# Schematic.net
KiCad netlist of a schematic drawn in Altium Designer
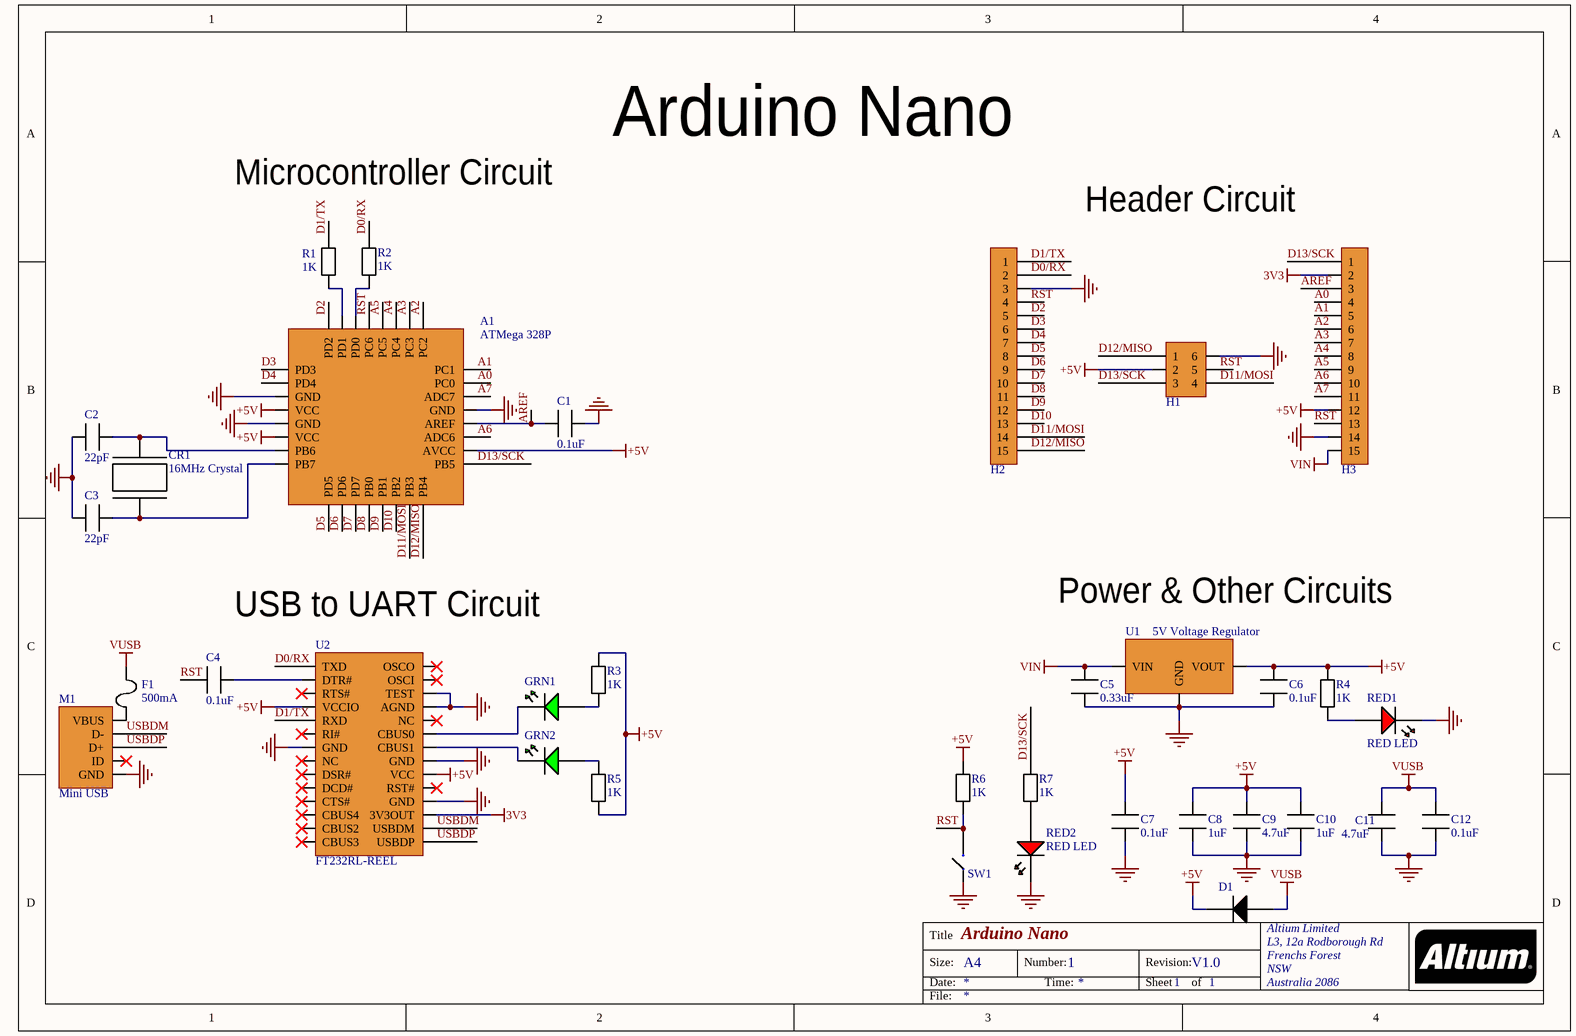
[diagram p0: Schematic.SchDoc]

(export (version "E")
  (design (tool "Eeschema 10.0.6"))
  (components
    (comp (ref "A1")
      (value "ATMega 328P")
      (footprint "ATmega 328P")
      (fields
        (field (name "MANUFACTURER") "Microchip / Atmel")
        (field (name "MANUFACTURER PART NUMBER") "ATMEGA328P-AUR")
      )
      (libsource (lib "Schematic Library") (part "ATMEGA328P-AUR"))
    )
    (comp (ref "C1")
      (value "0.1uF")
      (footprint "0.1uF Capacitor")
      (description "TAIYO YUDEN - EMK105BJ104KV-F - CERAMIC CAPACITOR, 0.1UF, 16V, X5R, 10%, 0402, FULL REEL")
      (fields
        (field (name "MANUFACTURER") "Taiyo Yuden")
        (field (name "MANUFACTURER PART NUMBER") "EMK105BJ104KV-F")
      )
      (libsource (lib "Schematic Library") (part "EMK105BJ104KV-F"))
    )
    (comp (ref "C2")
      (value "22pF")
      (footprint "22pF")
      (description "Cap Ceramic 22pF 50V C0G 1% SMD 0402 125C Paper T/R")
      (fields
        (field (name "MANUFACTURER") "Kyocera AVX")
        (field (name "MANUFACTURER PART NUMBER") "04025A220FAT2A")
      )
      (libsource (lib "Schematic Library") (part "04025A220FAT2A"))
    )
    (comp (ref "C3")
      (value "22pF")
      (footprint "22pF")
      (description "Cap Ceramic 22pF 50V C0G 1% SMD 0402 125C Paper T/R")
      (fields
        (field (name "MANUFACTURER") "Kyocera AVX")
        (field (name "MANUFACTURER PART NUMBER") "04025A220FAT2A")
      )
      (libsource (lib "Schematic Library") (part "04025A220FAT2A"))
    )
    (comp (ref "C4")
      (value "0.1uF")
      (footprint "0.1uF Capacitor")
      (description "TAIYO YUDEN - EMK105BJ104KV-F - CERAMIC CAPACITOR, 0.1UF, 16V, X5R, 10%, 0402, FULL REEL")
      (fields
        (field (name "MANUFACTURER") "Taiyo Yuden")
        (field (name "MANUFACTURER PART NUMBER") "EMK105BJ104KV-F")
      )
      (libsource (lib "Schematic Library") (part "EMK105BJ104KV-F"))
    )
    (comp (ref "C5")
      (value "0.33uF")
      (footprint "0.33uF Capacitor")
      (description "Automotive Grade")
      (fields
        (field (name "MANUFACTURER") "TDK")
        (field (name "MANUFACTURER PART NUMBER") "CGA2B1X7S1C334K050BC")
      )
      (libsource (lib "Schematic Library") (part "CGA2B1X7S1C334K050BC"))
    )
    (comp (ref "C6")
      (value "0.1uF")
      (footprint "0.1uF Capacitor")
      (description "TAIYO YUDEN - EMK105BJ104KV-F - CERAMIC CAPACITOR, 0.1UF, 16V, X5R, 10%, 0402, FULL REEL")
      (fields
        (field (name "MANUFACTURER") "Taiyo Yuden")
        (field (name "MANUFACTURER PART NUMBER") "EMK105BJ104KV-F")
      )
      (libsource (lib "Schematic Library") (part "EMK105BJ104KV-F"))
    )
    (comp (ref "C7")
      (value "0.1uF")
      (footprint "0.1uF Capacitor")
      (description "TAIYO YUDEN - EMK105BJ104KV-F - CERAMIC CAPACITOR, 0.1UF, 16V, X5R, 10%, 0402, FULL REEL")
      (fields
        (field (name "MANUFACTURER") "Taiyo Yuden")
        (field (name "MANUFACTURER PART NUMBER") "EMK105BJ104KV-F")
      )
      (libsource (lib "Schematic Library") (part "EMK105BJ104KV-F"))
    )
    (comp (ref "C8")
      (value "1uF")
      (footprint "1uF Capacitor")
      (description "LMK105BJ105KV-F")
      (fields (field (name "MANUFACTURER") "Taiyo Yuden") (field (name "TOLERANCE") "10%"))
      (libsource (lib "Schematic Library") (part "LMK105BJ105KV-F"))
    )
    (comp (ref "C9")
      (value "4.7uF")
      (footprint "4.7uF Capacitor")
      (description "CAP CER 4.7UF 6.3V X5R 0402")
      (fields
        (field (name "MANUFACTURER") "Taiyo Yuden")
        (field (name "MANUFACTURER PART NUMBER") "JMK105BBJ475MVHF")
      )
      (libsource (lib "Schematic Library") (part "JMK105BBJ475MVHF"))
    )
    (comp (ref "C10")
      (value "1uF")
      (footprint "1uF Capacitor")
      (description "LMK105BJ105KV-F")
      (fields (field (name "MANUFACTURER") "Taiyo Yuden") (field (name "TOLERANCE") "10%"))
      (libsource (lib "Schematic Library") (part "LMK105BJ105KV-F"))
    )
    (comp (ref "C11")
      (value "4.7uF")
      (footprint "4.7uF Capacitor")
      (description "CAP CER 4.7UF 6.3V X5R 0402")
      (fields
        (field (name "MANUFACTURER") "Taiyo Yuden")
        (field (name "MANUFACTURER PART NUMBER") "JMK105BBJ475MVHF")
      )
      (libsource (lib "Schematic Library") (part "JMK105BBJ475MVHF"))
    )
    (comp (ref "C12")
      (value "0.1uF")
      (footprint "0.1uF Capacitor")
      (description "TAIYO YUDEN - EMK105BJ104KV-F - CERAMIC CAPACITOR, 0.1UF, 16V, X5R, 10%, 0402, FULL REEL")
      (fields
        (field (name "MANUFACTURER") "Taiyo Yuden")
        (field (name "MANUFACTURER PART NUMBER") "EMK105BJ104KV-F")
      )
      (libsource (lib "Schematic Library") (part "EMK105BJ104KV-F"))
    )
    (comp (ref "CR1")
      (value "16MHz Crystal")
      (footprint "16MHz Crystal")
      (description "CRYSTAL 16.0000MHZ 20PF SMD")
      (fields
        (field (name "MANUFACTURER") "ECS International")
        (field (name "MANUFACTURER PART NUMBER") "ECS-160-20-5PX-TR")
      )
      (libsource (lib "Schematic Library") (part "ECS-160-20-5PX-TR"))
    )
    (comp (ref "D1")
      (value "Diode")
      (footprint "Diode")
      (description "MULTICOMP PRO - BAT54LP-7 - DIODE, ULTRAFAST RECOVERY, 100mA, 30V, DFN1006")
      (fields (field (name "MANUFACTURER") "Diodes") (field (name "MANUFACTURER PART NUMBER") "BAT54LP-7"))
      (libsource (lib "Schematic Library") (part "BAT54LP-7"))
    )
    (comp (ref "F1")
      (value "500mA")
      (footprint "Fuse")
      (description "Fuse Chip 0.5A 125V Very Fast 2-Pin Solder Pad Surface Mount T/R")
      (fields (field (name "MANUFACTURER") "Bel") (field (name "MANUFACTURER PART NUMBER") "C1Q500"))
      (libsource (lib "Schematic Library") (part "C1Q500"))
    )
    (comp (ref "GRN1")
      (value "GREEN LED")
      (footprint "GREEN LED")
      (description "LED GREEN CLEAR 0402 SMD")
      (fields
        (field (name "MANUFACTURER") "Wurth Electronics")
        (field (name "MANUFACTURER PART NUMBER") "150040VS73240")
      )
      (libsource (lib "Schematic Library") (part "150040VS73240"))
    )
    (comp (ref "GRN2")
      (value "GREEN LED")
      (footprint "GREEN LED")
      (description "LED GREEN CLEAR 0402 SMD")
      (fields
        (field (name "MANUFACTURER") "Wurth Electronics")
        (field (name "MANUFACTURER PART NUMBER") "150040VS73240")
      )
      (libsource (lib "Schematic Library") (part "150040VS73240"))
    )
    (comp (ref "H1")
      (value "3x3")
      (footprint "3x3 Header")
      (description "CONN HEADER VERT 6POS 2.54MM")
      (fields
        (field (name "MANUFACTURER") "Wurth Electronics")
        (field (name "MANUFACTURER PART NUMBER") "61300621121")
      )
      (libsource (lib "Schematic Library") (part "61300621121"))
    )
    (comp (ref "H2")
      (value "15x1")
      (footprint "15x1 Header")
      (fields
        (field (name "MANUFACTURER") "Wurth Electronics")
        (field (name "MANUFACTURER PART NUMBER") "61301511121")
      )
      (libsource (lib "") (part "61301511121_1"))
    )
    (comp (ref "H3")
      (value "15x1")
      (footprint "15x1 Header")
      (fields
        (field (name "MANUFACTURER") "Wurth Electronics")
        (field (name "MANUFACTURER PART NUMBER") "61301511121")
      )
      (libsource (lib "Schematic Library") (part "61301511121"))
    )
    (comp (ref "M1")
      (value "Mini USB")
      (footprint "Mini USB")
      (description "CONN RCPT USB2.0 MINI B SMD R/A")
      (fields
        (field (name "MANUFACTURER") "Wurth Electronics")
        (field (name "MANUFACTURER PART NUMBER") "65100516121")
      )
      (libsource (lib "Schematic Library") (part "65100516121"))
    )
    (comp (ref "R1")
      (value "1K")
      (footprint "1K Resistor")
      (description "RES 1K OHM 1% 1/16W 0402")
      (fields
        (field (name "MANUFACTURER") "Stackpole Electronics")
        (field (name "MANUFACTURER PART NUMBER") "RMCF0402FT1K00")
      )
      (libsource (lib "Schematic Library") (part "RMCF0402FT1K00"))
    )
    (comp (ref "R2")
      (value "1K")
      (footprint "1K Resistor")
      (description "RES 1K OHM 1% 1/16W 0402")
      (fields
        (field (name "MANUFACTURER") "Stackpole Electronics")
        (field (name "MANUFACTURER PART NUMBER") "RMCF0402FT1K00")
      )
      (libsource (lib "Schematic Library") (part "RMCF0402FT1K00"))
    )
    (comp (ref "R3")
      (value "1K")
      (footprint "1K Resistor")
      (description "RES 1K OHM 1% 1/16W 0402")
      (fields
        (field (name "MANUFACTURER") "Stackpole Electronics")
        (field (name "MANUFACTURER PART NUMBER") "RMCF0402FT1K00")
      )
      (libsource (lib "Schematic Library") (part "RMCF0402FT1K00"))
    )
    (comp (ref "R4")
      (value "1K")
      (footprint "1K Resistor")
      (description "RES 1K OHM 1% 1/16W 0402")
      (fields
        (field (name "MANUFACTURER") "Stackpole Electronics")
        (field (name "MANUFACTURER PART NUMBER") "RMCF0402FT1K00")
      )
      (libsource (lib "Schematic Library") (part "RMCF0402FT1K00"))
    )
    (comp (ref "R5")
      (value "1K")
      (footprint "1K Resistor")
      (description "RES 1K OHM 1% 1/16W 0402")
      (fields
        (field (name "MANUFACTURER") "Stackpole Electronics")
        (field (name "MANUFACTURER PART NUMBER") "RMCF0402FT1K00")
      )
      (libsource (lib "Schematic Library") (part "RMCF0402FT1K00"))
    )
    (comp (ref "R6")
      (value "1K")
      (footprint "1K Resistor")
      (description "RES 1K OHM 1% 1/16W 0402")
      (fields
        (field (name "MANUFACTURER") "Stackpole Electronics")
        (field (name "MANUFACTURER PART NUMBER") "RMCF0402FT1K00")
      )
      (libsource (lib "Schematic Library") (part "RMCF0402FT1K00"))
    )
    (comp (ref "R7")
      (value "1K")
      (footprint "1K Resistor")
      (description "RES 1K OHM 1% 1/16W 0402")
      (fields
        (field (name "MANUFACTURER") "Stackpole Electronics")
        (field (name "MANUFACTURER PART NUMBER") "RMCF0402FT1K00")
      )
      (libsource (lib "Schematic Library") (part "RMCF0402FT1K00"))
    )
    (comp (ref "RED1")
      (value "RED LED")
      (footprint "RED LED")
      (description "LED RED CLEAR 0402 SMD")
      (fields
        (field (name "MANUFACTURER") "Wurth Electronics")
        (field (name "MANUFACTURER PART NUMBER") "150040RS73240")
      )
      (libsource (lib "Schematic Library") (part "150040RS73240"))
    )
    (comp (ref "RED2")
      (value "RED LED")
      (footprint "RED LED")
      (description "LED RED CLEAR 0402 SMD")
      (fields
        (field (name "MANUFACTURER") "Wurth Electronics")
        (field (name "MANUFACTURER PART NUMBER") "150040RS73240")
      )
      (libsource (lib "Schematic Library") (part "150040RS73240"))
    )
    (comp (ref "SW1")
      (value "Push Button")
      (footprint "Push Button")
      (description "SWITCH TACTILE SPST-NO 0.05A 12V")
      (fields
        (field (name "MANUFACTURER") "Wurth Electronics")
        (field (name "MANUFACTURER PART NUMBER") "434121043836")
      )
      (libsource (lib "Schematic Library") (part "434121043836"))
    )
    (comp (ref "U1")
      (value "5V Voltage Regulator")
      (footprint "Voltage Regulator")
      (description "TEXAS INSTRUMENTS - UA78L05ACPK - LINEAR VOLT REG, 5V, 0.1A, SOT-89-3")
      (fields
        (field (name "MANUFACTURER") "Texas Instruments")
        (field (name "MANUFACTURER PART NUMBER") "UA78L05ACPK")
      )
      (libsource (lib "Schematic Library") (part "UA78L05ACPK"))
    )
    (comp (ref "U2")
      (value "FT232RL-REEL")
      (footprint "FTDI")
      (description "FTDI - FT232RL-REEL - Interface Bridges, USB to UART, 1.8 V, 5.25 V, SSOP, 28 Pins, -40 °C")
      (fields (field (name "MANUFACTURER") "FTDI") (field (name "VOLTAGE") "5V"))
      (libsource (lib "Schematic Library") (part "FT232RL-REEL"))
    )
  )
  (nets
    (net (code "1") (name "+5V") (class "Default")
      (node (ref "A1") (pin "18") (pinfunction "AVCC_18") (pintype "passive"))
      (node (ref "A1") (pin "4") (pinfunction "VCC_4") (pintype "passive"))
      (node (ref "A1") (pin "6") (pinfunction "VCC_6") (pintype "passive"))
      (node (ref "C10") (pin "2") (pinfunction "2_2") (pintype "passive"))
      (node (ref "C6") (pin "2") (pinfunction "2_2") (pintype "passive"))
      (node (ref "C7") (pin "1") (pinfunction "1_1") (pintype "passive"))
      (node (ref "C8") (pin "2") (pinfunction "2_2") (pintype "passive"))
      (node (ref "C9") (pin "2") (pinfunction "2_2") (pintype "passive"))
      (node (ref "D1") (pin "1") (pinfunction "1_1") (pintype "passive"))
      (node (ref "H1") (pin "2") (pinfunction "2_2") (pintype "passive"))
      (node (ref "H3") (pin "12") (pinfunction "12_12") (pintype "passive"))
      (node (ref "R3") (pin "2") (pinfunction "2_2") (pintype "passive"))
      (node (ref "R4") (pin "2") (pinfunction "2_2") (pintype "passive"))
      (node (ref "R5") (pin "1") (pinfunction "1_1") (pintype "passive"))
      (node (ref "R6") (pin "2") (pinfunction "2_2") (pintype "passive"))
      (node (ref "U1") (pin "3") (pinfunction "VOUT_3") (pintype "passive"))
      (node (ref "U2") (pin "20") (pinfunction "VCC_20") (pintype "passive"))
      (node (ref "U2") (pin "4") (pinfunction "VCCIO_4") (pintype "passive"))
    )
    (net (code "2") (name "/A0") (class "Default")
      (node (ref "A1") (pin "23") (pinfunction "PC0_23") (pintype "passive"))
      (node (ref "H3") (pin "4") (pinfunction "4_4") (pintype "passive"))
    )
    (net (code "3") (name "/A1") (class "Default")
      (node (ref "A1") (pin "24") (pinfunction "PC1_24") (pintype "passive"))
      (node (ref "H3") (pin "5") (pinfunction "5_5") (pintype "passive"))
    )
    (net (code "4") (name "/A2") (class "Default")
      (node (ref "A1") (pin "25") (pinfunction "PC2_25") (pintype "passive"))
      (node (ref "H3") (pin "6") (pinfunction "6_6") (pintype "passive"))
    )
    (net (code "5") (name "/A3") (class "Default")
      (node (ref "A1") (pin "26") (pinfunction "PC3_26") (pintype "passive"))
      (node (ref "H3") (pin "7") (pinfunction "7_7") (pintype "passive"))
    )
    (net (code "6") (name "/A4") (class "Default")
      (node (ref "A1") (pin "27") (pinfunction "PC4_27") (pintype "passive"))
      (node (ref "H3") (pin "8") (pinfunction "8_8") (pintype "passive"))
    )
    (net (code "7") (name "/A5") (class "Default")
      (node (ref "A1") (pin "28") (pinfunction "PC5_28") (pintype "passive"))
      (node (ref "H3") (pin "9") (pinfunction "9_9") (pintype "passive"))
    )
    (net (code "8") (name "/A6") (class "Default")
      (node (ref "A1") (pin "19") (pinfunction "ADC6_19") (pintype "passive"))
      (node (ref "H3") (pin "10") (pinfunction "10_10") (pintype "passive"))
    )
    (net (code "9") (name "/A7") (class "Default")
      (node (ref "A1") (pin "22") (pinfunction "ADC7_22") (pintype "passive"))
      (node (ref "H3") (pin "11") (pinfunction "11_11") (pintype "passive"))
    )
    (net (code "10") (name "/AREF") (class "Default")
      (node (ref "A1") (pin "20") (pinfunction "AREF_20") (pintype "passive"))
      (node (ref "C1") (pin "1") (pinfunction "1_1") (pintype "passive"))
      (node (ref "H3") (pin "3") (pinfunction "3_3") (pintype "passive"))
    )
    (net (code "11") (name "/D0{slash}RX") (class "Default")
      (node (ref "H2") (pin "2") (pinfunction "2_2") (pintype "passive"))
      (node (ref "R2") (pin "1") (pinfunction "1_1") (pintype "passive"))
      (node (ref "U2") (pin "1") (pinfunction "TXD_1") (pintype "passive"))
    )
    (net (code "12") (name "/D1{slash}TX") (class "Default")
      (node (ref "H2") (pin "1") (pinfunction "1_1") (pintype "passive"))
      (node (ref "R1") (pin "2") (pinfunction "2_2") (pintype "passive"))
      (node (ref "U2") (pin "5") (pinfunction "RXD_5") (pintype "passive"))
    )
    (net (code "13") (name "/D2") (class "Default")
      (node (ref "A1") (pin "32") (pinfunction "PD2_32") (pintype "passive"))
      (node (ref "H2") (pin "5") (pinfunction "5_5") (pintype "passive"))
    )
    (net (code "14") (name "/D3") (class "Default")
      (node (ref "A1") (pin "1") (pinfunction "PD3_1") (pintype "passive"))
      (node (ref "H2") (pin "6") (pinfunction "6_6") (pintype "passive"))
    )
    (net (code "15") (name "/D4") (class "Default")
      (node (ref "A1") (pin "2") (pinfunction "PD4_2") (pintype "passive"))
      (node (ref "H2") (pin "7") (pinfunction "7_7") (pintype "passive"))
    )
    (net (code "16") (name "/D5") (class "Default")
      (node (ref "A1") (pin "9") (pinfunction "PD5_9") (pintype "passive"))
      (node (ref "H2") (pin "8") (pinfunction "8_8") (pintype "passive"))
    )
    (net (code "17") (name "/D6") (class "Default")
      (node (ref "A1") (pin "10") (pinfunction "PD6_10") (pintype "passive"))
      (node (ref "H2") (pin "9") (pinfunction "9_9") (pintype "passive"))
    )
    (net (code "18") (name "/D7") (class "Default")
      (node (ref "A1") (pin "11") (pinfunction "PD7_11") (pintype "passive"))
      (node (ref "H2") (pin "10") (pinfunction "10_10") (pintype "passive"))
    )
    (net (code "19") (name "/D8") (class "Default")
      (node (ref "A1") (pin "12") (pinfunction "PB0_12") (pintype "passive"))
      (node (ref "H2") (pin "11") (pinfunction "11_11") (pintype "passive"))
    )
    (net (code "20") (name "/D9") (class "Default")
      (node (ref "A1") (pin "13") (pinfunction "PB1_13") (pintype "passive"))
      (node (ref "H2") (pin "12") (pinfunction "12_12") (pintype "passive"))
    )
    (net (code "21") (name "/D10") (class "Default")
      (node (ref "A1") (pin "14") (pinfunction "PB2_14") (pintype "passive"))
      (node (ref "H2") (pin "13") (pinfunction "13_13") (pintype "passive"))
    )
    (net (code "22") (name "/D11{slash}MOSI") (class "Default")
      (node (ref "A1") (pin "15") (pinfunction "PB3_15") (pintype "passive"))
      (node (ref "H1") (pin "4") (pinfunction "4_4") (pintype "passive"))
      (node (ref "H2") (pin "14") (pinfunction "14_14") (pintype "passive"))
    )
    (net (code "23") (name "/D12{slash}MISO") (class "Default")
      (node (ref "A1") (pin "16") (pinfunction "PB4_16") (pintype "passive"))
      (node (ref "H1") (pin "1") (pinfunction "1_1") (pintype "passive"))
      (node (ref "H2") (pin "15") (pinfunction "15_15") (pintype "passive"))
    )
    (net (code "24") (name "/D13{slash}SCK") (class "Default")
      (node (ref "A1") (pin "17") (pinfunction "PB5_17") (pintype "passive"))
      (node (ref "H1") (pin "3") (pinfunction "3_3") (pintype "passive"))
      (node (ref "H3") (pin "1") (pinfunction "1_1") (pintype "passive"))
      (node (ref "R7") (pin "2") (pinfunction "2_2") (pintype "passive"))
    )
    (net (code "25") (name "/RST") (class "Default")
      (node (ref "A1") (pin "29") (pinfunction "PC6_29") (pintype "passive"))
      (node (ref "C4") (pin "1") (pinfunction "1_1") (pintype "passive"))
      (node (ref "H1") (pin "5") (pinfunction "5_5") (pintype "passive"))
      (node (ref "H2") (pin "4") (pinfunction "4_4") (pintype "passive"))
      (node (ref "H3") (pin "13") (pinfunction "13_13") (pintype "passive"))
      (node (ref "R6") (pin "1") (pinfunction "1_1") (pintype "passive"))
      (node (ref "SW1") (pin "2") (pinfunction "2_2") (pintype "passive"))
    )
    (net (code "26") (name "/USBDM") (class "Default")
      (node (ref "M1") (pin "2") (pinfunction "D-_2") (pintype "passive"))
      (node (ref "U2") (pin "16") (pinfunction "USBDM_16") (pintype "passive"))
    )
    (net (code "27") (name "/USBDP") (class "Default")
      (node (ref "M1") (pin "3") (pinfunction "D+_3") (pintype "passive"))
      (node (ref "U2") (pin "15") (pinfunction "USBDP_15") (pintype "passive"))
    )
    (net (code "28") (name "3V3") (class "Default")
      (node (ref "H3") (pin "2") (pinfunction "2_2") (pintype "passive"))
      (node (ref "U2") (pin "17") (pinfunction "3V3OUT_17") (pintype "passive"))
    )
    (net (code "29") (name "GND") (class "Default")
      (node (ref "A1") (pin "21") (pinfunction "GND_21") (pintype "passive"))
      (node (ref "A1") (pin "3") (pinfunction "GND_3") (pintype "passive"))
      (node (ref "A1") (pin "5") (pinfunction "GND_5") (pintype "passive"))
      (node (ref "C1") (pin "2") (pinfunction "2_2") (pintype "passive"))
      (node (ref "C10") (pin "1") (pinfunction "1_1") (pintype "passive"))
      (node (ref "C11") (pin "1") (pinfunction "1_1") (pintype "passive"))
      (node (ref "C12") (pin "1") (pinfunction "1_1") (pintype "passive"))
      (node (ref "C2") (pin "1") (pinfunction "1_1") (pintype "passive"))
      (node (ref "C3") (pin "2") (pinfunction "2_2") (pintype "passive"))
      (node (ref "C5") (pin "1") (pinfunction "1_1") (pintype "passive"))
      (node (ref "C6") (pin "1") (pinfunction "1_1") (pintype "passive"))
      (node (ref "C7") (pin "2") (pinfunction "2_2") (pintype "passive"))
      (node (ref "C8") (pin "1") (pinfunction "1_1") (pintype "passive"))
      (node (ref "C9") (pin "1") (pinfunction "1_1") (pintype "passive"))
      (node (ref "H1") (pin "6") (pinfunction "6_6") (pintype "passive"))
      (node (ref "H2") (pin "3") (pinfunction "3_3") (pintype "passive"))
      (node (ref "H3") (pin "14") (pinfunction "14_14") (pintype "passive"))
      (node (ref "M1") (pin "5") (pinfunction "GND_5") (pintype "passive"))
      (node (ref "RED1") (pin "1") (pinfunction "1_1") (pintype "passive"))
      (node (ref "RED2") (pin "1") (pinfunction "1_1") (pintype "passive"))
      (node (ref "SW1") (pin "1") (pinfunction "1_1") (pintype "passive"))
      (node (ref "U1") (pin "2") (pinfunction "GND_2") (pintype "passive"))
      (node (ref "U2") (pin "18") (pinfunction "GND_18") (pintype "passive"))
      (node (ref "U2") (pin "21") (pinfunction "GND_21") (pintype "passive"))
      (node (ref "U2") (pin "25") (pinfunction "AGND_25") (pintype "passive"))
      (node (ref "U2") (pin "26") (pinfunction "TEST_26") (pintype "passive"))
      (node (ref "U2") (pin "7") (pinfunction "GND_7") (pintype "passive"))
    )
    (net (code "30") (name "Net-(A1-PB6)") (class "Default")
      (node (ref "A1") (pin "7") (pinfunction "PB6_7") (pintype "passive"))
      (node (ref "C2") (pin "2") (pinfunction "2_2") (pintype "passive"))
      (node (ref "CR1") (pin "1") (pinfunction "1_1") (pintype "passive"))
    )
    (net (code "31") (name "Net-(A1-PB7)") (class "Default")
      (node (ref "A1") (pin "8") (pinfunction "PB7_8") (pintype "passive"))
      (node (ref "C3") (pin "1") (pinfunction "1_1") (pintype "passive"))
      (node (ref "CR1") (pin "2") (pinfunction "2_2") (pintype "passive"))
    )
    (net (code "32") (name "Net-(A1-PD0)") (class "Default")
      (node (ref "A1") (pin "30") (pinfunction "PD0_30") (pintype "passive"))
      (node (ref "R2") (pin "2") (pinfunction "2_2") (pintype "passive"))
    )
    (net (code "33") (name "Net-(A1-PD1)") (class "Default")
      (node (ref "A1") (pin "31") (pinfunction "PD1_31") (pintype "passive"))
      (node (ref "R1") (pin "1") (pinfunction "1_1") (pintype "passive"))
    )
    (net (code "34") (name "Net-(GRN1-Pad2)") (class "Default")
      (node (ref "GRN1") (pin "2") (pinfunction "2_2") (pintype "passive"))
      (node (ref "R3") (pin "1") (pinfunction "1_1") (pintype "passive"))
    )
    (net (code "35") (name "Net-(GRN2-Pad2)") (class "Default")
      (node (ref "GRN2") (pin "2") (pinfunction "2_2") (pintype "passive"))
      (node (ref "R5") (pin "2") (pinfunction "2_2") (pintype "passive"))
    )
    (net (code "36") (name "Net-(M1-VBUS)") (class "Default")
      (node (ref "F1") (pin "1") (pinfunction "1_1") (pintype "passive"))
      (node (ref "M1") (pin "1") (pinfunction "VBUS_1") (pintype "passive"))
    )
    (net (code "37") (name "Net-(R4-Pad1)") (class "Default")
      (node (ref "R4") (pin "1") (pinfunction "1_1") (pintype "passive"))
      (node (ref "RED1") (pin "2") (pinfunction "2_2") (pintype "passive"))
    )
    (net (code "38") (name "Net-(R7-Pad1)") (class "Default")
      (node (ref "R7") (pin "1") (pinfunction "1_1") (pintype "passive"))
      (node (ref "RED2") (pin "2") (pinfunction "2_2") (pintype "passive"))
    )
    (net (code "39") (name "Net-(U2-CBUS0)") (class "Default")
      (node (ref "GRN1") (pin "1") (pinfunction "1_1") (pintype "passive"))
      (node (ref "U2") (pin "23") (pinfunction "CBUS0_23") (pintype "passive"))
    )
    (net (code "40") (name "Net-(U2-CBUS1)") (class "Default")
      (node (ref "GRN2") (pin "1") (pinfunction "1_1") (pintype "passive"))
      (node (ref "U2") (pin "22") (pinfunction "CBUS1_22") (pintype "passive"))
    )
    (net (code "41") (name "Net-(U2-DTR#)") (class "Default")
      (node (ref "C4") (pin "2") (pinfunction "2_2") (pintype "passive"))
      (node (ref "U2") (pin "2") (pinfunction "DTR#_2") (pintype "passive"))
    )
    (net (code "42") (name "VIN") (class "Default")
      (node (ref "C5") (pin "2") (pinfunction "2_2") (pintype "passive"))
      (node (ref "H3") (pin "15") (pinfunction "15_15") (pintype "passive"))
      (node (ref "U1") (pin "1") (pinfunction "VIN_1") (pintype "passive"))
    )
    (net (code "43") (name "VUSB") (class "Default")
      (node (ref "C11") (pin "2") (pinfunction "2_2") (pintype "passive"))
      (node (ref "C12") (pin "2") (pinfunction "2_2") (pintype "passive"))
      (node (ref "D1") (pin "2") (pinfunction "2_2") (pintype "passive"))
      (node (ref "F1") (pin "2") (pinfunction "2_2") (pintype "passive"))
    )
    (net (code "44") (name "unconnected-(M1-ID-Pad4)") (class "Default")
      (node (ref "M1") (pin "4") (pinfunction "ID_4") (pintype "passive+no_connect"))
    )
    (net (code "45") (name "unconnected-(U2-CBUS2-Pad13)") (class "Default")
      (node (ref "U2") (pin "13") (pinfunction "CBUS2_13") (pintype "passive+no_connect"))
    )
    (net (code "46") (name "unconnected-(U2-CBUS3-Pad14)") (class "Default")
      (node (ref "U2") (pin "14") (pinfunction "CBUS3_14") (pintype "passive+no_connect"))
    )
    (net (code "47") (name "unconnected-(U2-CBUS4-Pad12)") (class "Default")
      (node (ref "U2") (pin "12") (pinfunction "CBUS4_12") (pintype "passive+no_connect"))
    )
    (net (code "48") (name "unconnected-(U2-CTS#-Pad11)") (class "Default")
      (node (ref "U2") (pin "11") (pinfunction "CTS#_11") (pintype "passive+no_connect"))
    )
    (net (code "49") (name "unconnected-(U2-DCD#-Pad10)") (class "Default")
      (node (ref "U2") (pin "10") (pinfunction "DCD#_10") (pintype "passive+no_connect"))
    )
    (net (code "50") (name "unconnected-(U2-DSR#-Pad9)") (class "Default")
      (node (ref "U2") (pin "9") (pinfunction "DSR#_9") (pintype "passive+no_connect"))
    )
    (net (code "51") (name "unconnected-(U2-NC-Pad8)") (class "Default")
      (node (ref "U2") (pin "8") (pinfunction "NC_8") (pintype "passive+no_connect"))
    )
    (net (code "52") (name "unconnected-(U2-NC-Pad24)") (class "Default")
      (node (ref "U2") (pin "24") (pinfunction "NC_24") (pintype "passive+no_connect"))
    )
    (net (code "53") (name "unconnected-(U2-OSCI-Pad27)") (class "Default")
      (node (ref "U2") (pin "27") (pinfunction "OSCI_27") (pintype "passive+no_connect"))
    )
    (net (code "54") (name "unconnected-(U2-OSCO-Pad28)") (class "Default")
      (node (ref "U2") (pin "28") (pinfunction "OSCO_28") (pintype "passive+no_connect"))
    )
    (net (code "55") (name "unconnected-(U2-RI#-Pad6)") (class "Default")
      (node (ref "U2") (pin "6") (pinfunction "RI#_6") (pintype "passive+no_connect"))
    )
    (net (code "56") (name "unconnected-(U2-RST#-Pad19)") (class "Default")
      (node (ref "U2") (pin "19") (pinfunction "RST#_19") (pintype "passive+no_connect"))
    )
    (net (code "57") (name "unconnected-(U2-RTS#-Pad3)") (class "Default")
      (node (ref "U2") (pin "3") (pinfunction "RTS#_3") (pintype "passive+no_connect"))
    )
  )
)
